# LB_BIT_i13_LIGHTSENSOR-v02_rev1_01.net
KiCad netlist of a schematic drawn in EAGLE
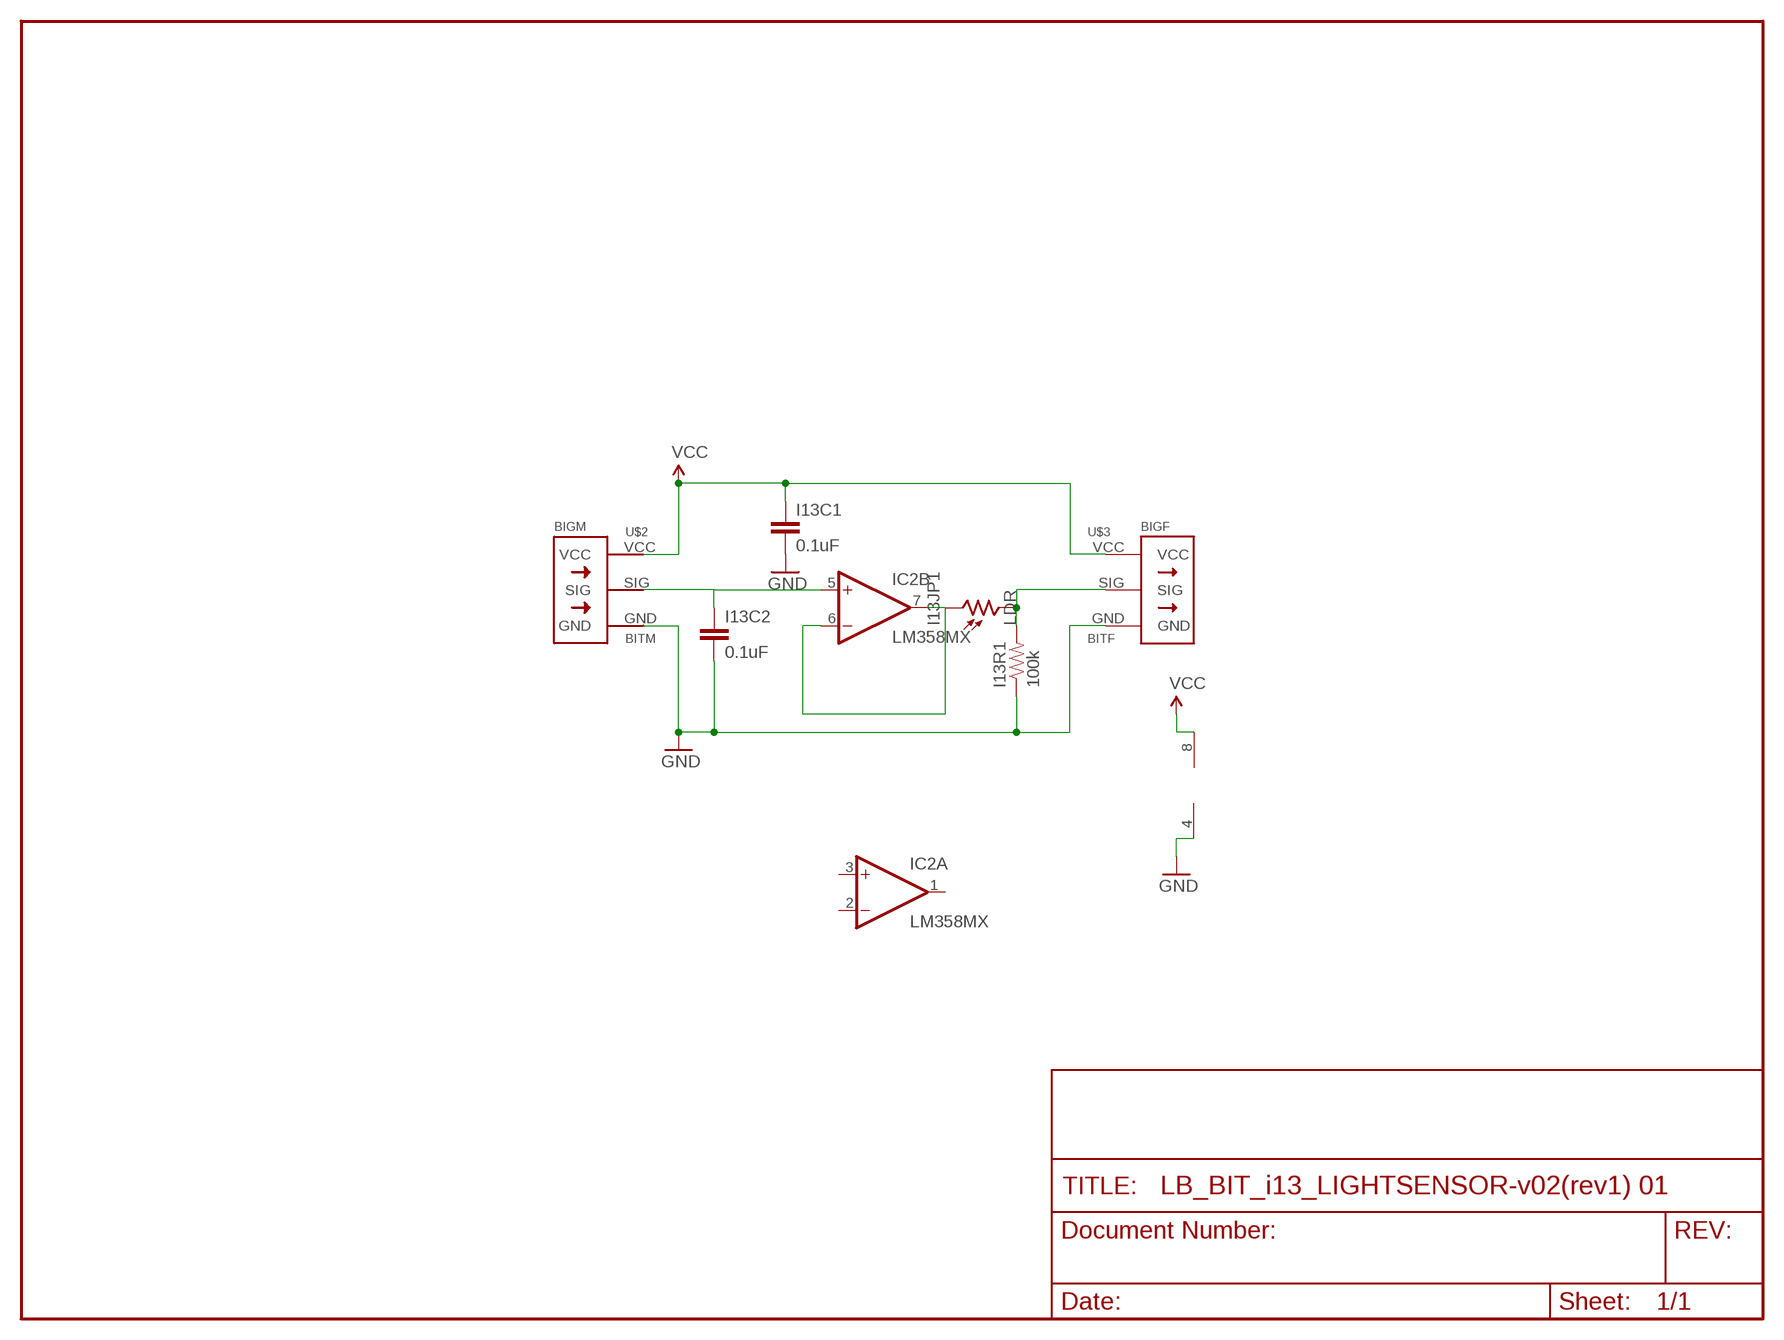
[diagram p0: schematic, sheet 1]

(export (version "E")
  (design (tool "Eeschema 10.0.6"))
  (components
    (comp (ref "I13C1")
      (value "0.1uF")
      (footprint "eagle-import:1206")
      (libsource (lib "eagle-import") (part "CAP1206"))
    )
    (comp (ref "I13C2")
      (value "0.1uF")
      (footprint "eagle-import:1206")
      (libsource (lib "eagle-import") (part "CAP1206"))
    )
    (comp (ref "I13JP1")
      (value "LDR")
      (footprint "eagle-import:T0-46-A10XX")
      (libsource (lib "eagle-import") (part "A1050_09"))
    )
    (comp (ref "I13R1")
      (value "100k")
      (footprint "eagle-import:0805")
      (libsource (lib "eagle-import") (part "RESISTOR0805-RES"))
    )
    (comp (ref "IC2")
      (value "LM358MX")
      (footprint "eagle-import:SO08")
      (libsource (lib "eagle-import") (part "LM358MX"))
    )
    (comp (ref "U$2")
      (value "BITM")
      (footprint "eagle-import:BITM")
      (libsource (lib "eagle-import") (part "BITM"))
    )
    (comp (ref "U$3")
      (value "BITF")
      (footprint "eagle-import:BITM")
      (libsource (lib "eagle-import") (part "BITF"))
    )
  )
  (nets
    (net (code "1") (name "GND") (class "Default")
      (node (ref "I13C1") (pin "2") (pinfunction "2_2") (pintype "passive"))
      (node (ref "I13C2") (pin "2") (pinfunction "2_2") (pintype "passive"))
      (node (ref "I13R1") (pin "1") (pinfunction "1_1") (pintype "passive"))
      (node (ref "IC2") (pin "4") (pinfunction "V-_4") (pintype "power_in"))
      (node (ref "U$2") (pin "GND") (pinfunction "GND_GND") (pintype "bidirectional"))
      (node (ref "U$3") (pin "GND") (pinfunction "GND_GND") (pintype "bidirectional"))
    )
    (net (code "2") (name "Net-(I13JP1-Pad2)") (class "Default")
      (node (ref "I13JP1") (pin "2") (pinfunction "2_2") (pintype "passive"))
      (node (ref "I13R1") (pin "2") (pinfunction "2_2") (pintype "passive"))
      (node (ref "U$3") (pin "SIG") (pinfunction "SIG_SIG") (pintype "bidirectional"))
    )
    (net (code "3") (name "Net-(IC2B-+IN)") (class "Default")
      (node (ref "I13C2") (pin "1") (pinfunction "1_1") (pintype "passive"))
      (node (ref "IC2") (pin "5") (pinfunction "+IN_5") (pintype "input"))
      (node (ref "U$2") (pin "SIG") (pinfunction "SIG_SIG") (pintype "bidirectional"))
    )
    (net (code "4") (name "Net-(IC2B--IN)") (class "Default")
      (node (ref "I13JP1") (pin "1") (pinfunction "1_1") (pintype "passive"))
      (node (ref "IC2") (pin "6") (pinfunction "-IN_6") (pintype "input"))
      (node (ref "IC2") (pin "7") (pinfunction "OUT_7") (pintype "output"))
    )
    (net (code "5") (name "VCC") (class "Default")
      (node (ref "I13C1") (pin "1") (pinfunction "1_1") (pintype "passive"))
      (node (ref "IC2") (pin "8") (pinfunction "V+_8") (pintype "power_in"))
      (node (ref "U$2") (pin "VCC") (pinfunction "VCC_VCC") (pintype "bidirectional"))
      (node (ref "U$3") (pin "VCC") (pinfunction "VCC_VCC") (pintype "bidirectional"))
    )
    (net (code "6") (name "unconnected-(IC2A-+IN-Pad3)") (class "Default")
      (node (ref "IC2") (pin "3") (pinfunction "+IN_3") (pintype "input"))
    )
    (net (code "7") (name "unconnected-(IC2A--IN-Pad2)") (class "Default")
      (node (ref "IC2") (pin "2") (pinfunction "-IN_2") (pintype "input"))
    )
    (net (code "8") (name "unconnected-(IC2A-OUT-Pad1)") (class "Default")
      (node (ref "IC2") (pin "1") (pinfunction "OUT_1") (pintype "output"))
    )
  )
)
